# Voeding.net
KiCad netlist of a schematic drawn in Altium Designer
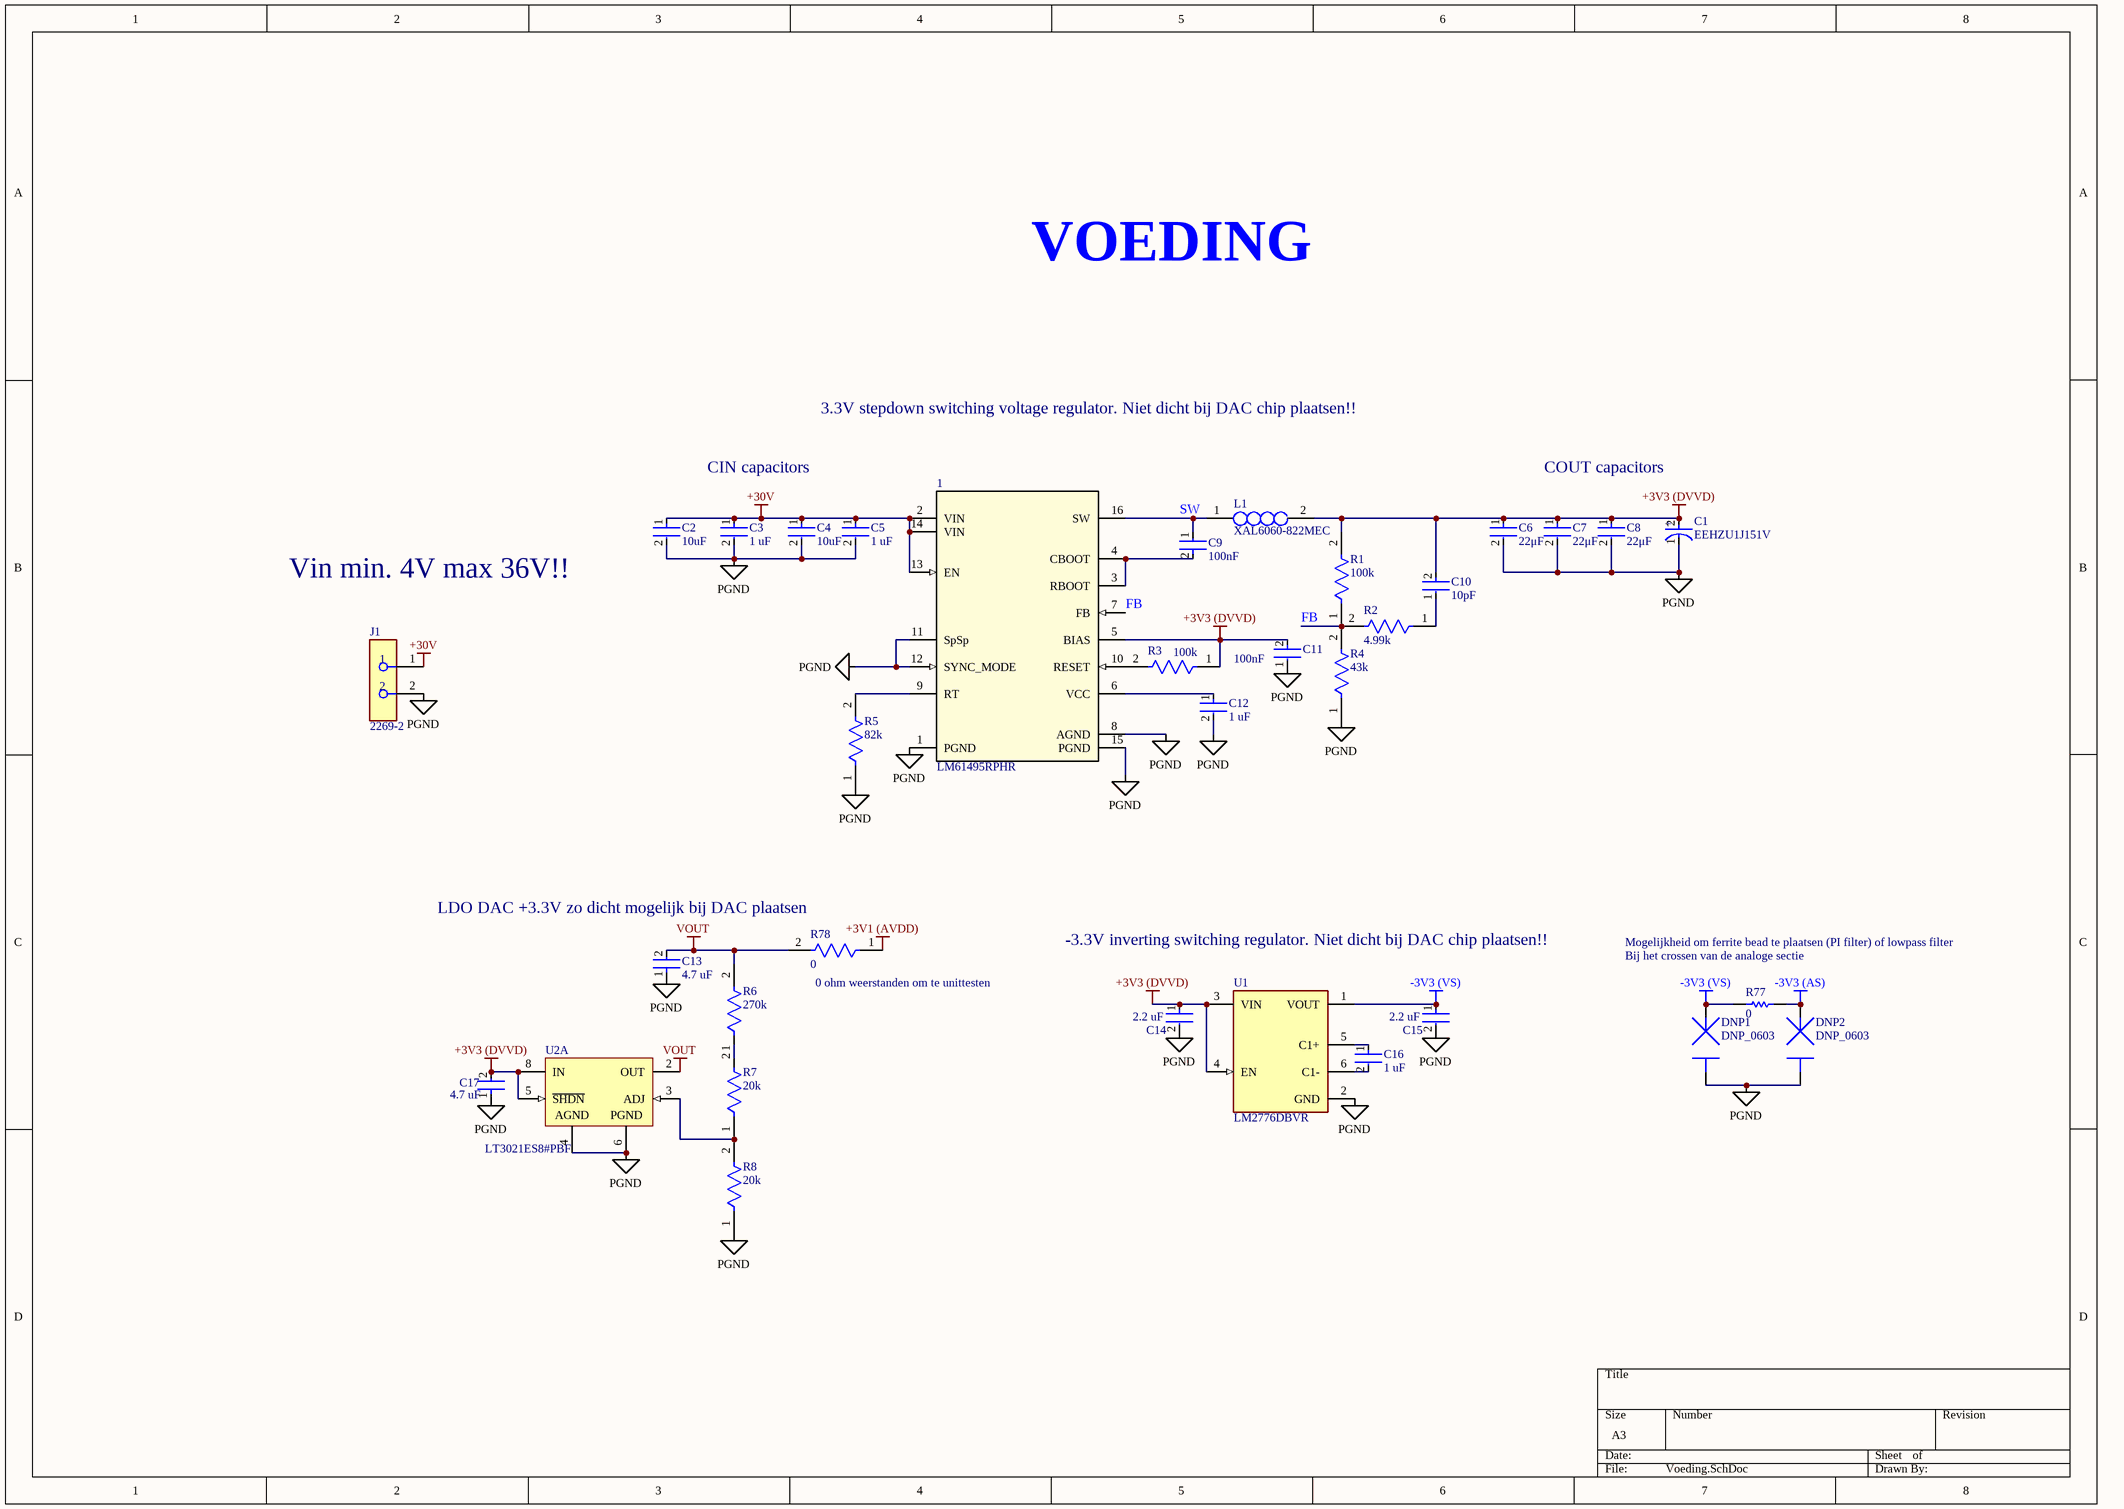
[diagram p0: Voeding.SchDoc]

(export (version "E")
  (design (tool "Eeschema 10.0.6"))
  (components
    (comp (ref "1")
      (value "LM61495RPHR")
      (footprint "RPH0016A")
      (description "No Description Available")
      (libsource (lib "LM61495RPHR") (part "LM61495RPHR"))
    )
    (comp (ref "C1")
      (value "EEHZU1J151V")
      (footprint "FP-EEH-G16-V-MFG")
      (description "Aluminum Hybrid Polymer Capacitors 150uF 20% 63V Life 4000Hours AEC-Q200 RADIAL SMT")
      (libsource (lib "Altium Content Vault") (part "203bc49f2ac43e59fd269a8c329ed05"))
    )
    (comp (ref "C2")
      (value "10uF")
      (footprint "FP-GRM32-MFG")
      (description "CAP CER 10UF 50V X7R 1210")
      (fields (field (name "TOLERANCE") "10%") (field (name "MANUFACTURER PART NUMBER") "GRM32ER71H106KA12L"))
      (libsource (lib "Altium Content Vault") (part "11868f565c42a9108669ba33697ecf6"))
    )
    (comp (ref "C3")
      (value "1 uF")
      (footprint "FP-C0603C-CF-MFG")
      (description "CAP CER 1 UF 50V 5% X7R 0603")
      (fields (field (name "TOLERANCE") "0.05") (field (name "MANUFACTURER PART NUMBER") "C0603C104J5RACTU"))
      (libsource (lib "Altium Content Vault") (part "b4654b650e69147ec39a6b967a45e02"))
    )
    (comp (ref "C4")
      (value "10uF")
      (footprint "FP-GRM32-MFG")
      (description "CAP CER 10UF 50V X7R 1210")
      (fields (field (name "TOLERANCE") "10%") (field (name "MANUFACTURER PART NUMBER") "GRM32ER71H106KA12L"))
      (libsource (lib "Altium Content Vault") (part "11868f565c42a9108669ba33697ecf6"))
    )
    (comp (ref "C5")
      (value "1 uF")
      (footprint "FP-C0603C-CF-MFG")
      (description "CAP CER 1 UF 50V 5% X7R 0603")
      (fields (field (name "TOLERANCE") "0.05") (field (name "MANUFACTURER PART NUMBER") "C0603C104J5RACTU"))
      (libsource (lib "Altium Content Vault") (part "b4654b650e69147ec39a6b967a45e02"))
    )
    (comp (ref "C6")
      (value "22μF")
      (footprint "FP-C2012-125-0_2-MFG")
      (description "Multilayer Ceramic Capacitors 22μF ±20% 10V X5R SMD 0805")
      (fields (field (name "TOLERANCE") "20%"))
      (libsource (lib "Altium Content Vault") (part "b4654b650e69147ec39a6b967a45e02"))
    )
    (comp (ref "C7")
      (value "22μF")
      (footprint "FP-C2012-125-0_2-MFG")
      (description "Multilayer Ceramic Capacitors 22μF ±20% 10V X5R SMD 0805")
      (fields (field (name "TOLERANCE") "20%"))
      (libsource (lib "Altium Content Vault") (part "b4654b650e69147ec39a6b967a45e02"))
    )
    (comp (ref "C8")
      (value "22μF")
      (footprint "FP-C2012-125-0_2-MFG")
      (description "Multilayer Ceramic Capacitors 22μF ±20% 10V X5R SMD 0805")
      (fields (field (name "TOLERANCE") "20%"))
      (libsource (lib "Altium Content Vault") (part "b4654b650e69147ec39a6b967a45e02"))
    )
    (comp (ref "C9")
      (value "100nF")
      (footprint "FP-GRM15-MFG")
      (description "CAP CER 0.1UF 16V X7R 0402")
      (fields (field (name "MANUFACTURER PART NUMBER") "GRM155R71C104KA88D") (field (name "TOLERANCE") "10%"))
      (libsource (lib "Altium Content Vault") (part "236180d848d6139a670b325ea6854c9"))
    )
    (comp (ref "C10")
      (value "10pF")
      (footprint "FP-GRM15-MFG")
      (description "CAP CER 10pF 16V X7R 0402")
      (fields (field (name "MANUFACTURER PART NUMBER") "GRM155R71C104KA88D") (field (name "TOLERANCE") "10%"))
      (libsource (lib "Altium Content Vault") (part "236180d848d6139a670b325ea6854c9"))
    )
    (comp (ref "C11")
      (value "100nF")
      (footprint "FP-GRM15-MFG")
      (description "CAP CER 0.1UF 16V X7R 0402")
      (fields (field (name "MANUFACTURER PART NUMBER") "GRM155R71C104KA88D") (field (name "TOLERANCE") "10%"))
      (libsource (lib "Altium Content Vault") (part "236180d848d6139a670b325ea6854c9"))
    )
    (comp (ref "C12")
      (value "1 uF")
      (footprint "FP-C0603C-CF-MFG")
      (description "CAP CER 1 UF 50V 5% X7R 0603")
      (fields (field (name "TOLERANCE") "0.05") (field (name "MANUFACTURER PART NUMBER") "C0603C104J5RACTU"))
      (libsource (lib "Altium Content Vault") (part "b4654b650e69147ec39a6b967a45e02"))
    )
    (comp (ref "C13")
      (value "4.7 uF")
      (footprint "FP-C0603C-CF-MFG")
      (description "CAP CER 4.7 UF 50V 5% X7R 0603")
      (fields (field (name "TOLERANCE") "0.05") (field (name "MANUFACTURER PART NUMBER") "C0603C104J5RACTU"))
      (libsource (lib "Altium Content Vault") (part "b4654b650e69147ec39a6b967a45e02"))
    )
    (comp (ref "C14")
      (value "2.2 uF")
      (footprint "FP-C0603C-CF-MFG")
      (description "CAP CER 2.2 UF 50V 5% X7R 0603")
      (fields (field (name "TOLERANCE") "0.05") (field (name "MANUFACTURER PART NUMBER") "C0603C104J5RACTU"))
      (libsource (lib "Altium Content Vault") (part "b4654b650e69147ec39a6b967a45e02"))
    )
    (comp (ref "C15")
      (value "2.2 uF")
      (footprint "FP-C0603C-CF-MFG")
      (description "CAP CER 2.2 UF 50V 5% X7R 0603")
      (fields (field (name "TOLERANCE") "0.05") (field (name "MANUFACTURER PART NUMBER") "C0603C104J5RACTU"))
      (libsource (lib "Altium Content Vault") (part "b4654b650e69147ec39a6b967a45e02"))
    )
    (comp (ref "C16")
      (value "1 uF")
      (footprint "FP-C0603C-CF-MFG")
      (description "CAP CER 1 UF 50V 5% X7R 0603")
      (fields (field (name "TOLERANCE") "0.05") (field (name "MANUFACTURER PART NUMBER") "C0603C104J5RACTU"))
      (libsource (lib "Altium Content Vault") (part "b4654b650e69147ec39a6b967a45e02"))
    )
    (comp (ref "C17")
      (value "4.7 uF")
      (footprint "FP-C0603C-CF-MFG")
      (description "CAP CER 4.7 UF 50V 5% X7R 0603")
      (fields (field (name "TOLERANCE") "0.05") (field (name "MANUFACTURER PART NUMBER") "C0603C104J5RACTU"))
      (libsource (lib "Altium Content Vault") (part "b4654b650e69147ec39a6b967a45e02"))
    )
    (comp (ref "DNP1")
      (value "DNP_0603")
      (footprint "DNP_0603_footprint")
      (description "Is just 0603 footprint. So that you can solder 0603 components on it after you ordered youre PCB.")
      (libsource (lib "Schlib2") (part "DNP_0603"))
    )
    (comp (ref "DNP2")
      (value "DNP_0603")
      (footprint "DNP_0603_footprint")
      (description "Is just 0603 footprint. So that you can solder 0603 components on it after you ordered youre PCB.")
      (libsource (lib "Schlib2") (part "DNP_0603"))
    )
    (comp (ref "J1")
      (value "2269-2")
      (footprint "FP-2269-2-MFG")
      (description "CONN DBL BANANA JACK TURRET")
      (libsource (lib "Altium Content Vault") (part "3ddab50f66188bb7952c54a1b76274c"))
    )
    (comp (ref "L1")
      (value "XAL6060-822MEC")
      (footprint "SamacSys:XAL6060822MEC")
      (description "8.2 uH Inductor")
      (fields (field (name "MOUSER PART NUMBER") "994-XAL6060-822MEC"))
      (libsource (lib "*") (part "XAL6060-822MEC"))
    )
    (comp (ref "R1")
      (value "100k")
      (footprint "FP-CRCW0402-C-e3-MFG")
      (description "RES 100K OHM 1% 1/16W 0402")
      (fields (field (name "TOLERANCE") "1%"))
      (libsource (lib "Altium Content Vault") (part "1029c3af85768c4190bb7ad29bc67b5"))
    )
    (comp (ref "R2")
      (value "4.99k")
      (footprint "FP-CRCW0402-e3-MFG")
      (description "RES Thick Film, 4.99kΩ, 1%, 0.063W, 100ppm/°C, 0402")
      (fields (field (name "TOLERANCE") "1%"))
      (libsource (lib "Altium Content Vault") (part "1029c3af85768c4190bb7ad29bc67b5"))
    )
    (comp (ref "R3")
      (value "100k")
      (footprint "FP-CRCW0402-C-e3-MFG")
      (description "RES 100K OHM 1% 1/16W 0402")
      (fields (field (name "TOLERANCE") "1%"))
      (libsource (lib "Altium Content Vault") (part "1029c3af85768c4190bb7ad29bc67b5"))
    )
    (comp (ref "R4")
      (value "43k")
      (footprint "FP-CRCW0402-C-e3-MFG")
      (description "RES 43k OHM 1% 1/16W 0402")
      (fields (field (name "TOLERANCE") "1%"))
      (libsource (lib "Altium Content Vault") (part "1029c3af85768c4190bb7ad29bc67b5"))
    )
    (comp (ref "R5")
      (value "82k")
      (footprint "FP-CRCW0402-C-e3-MFG")
      (description "RES 100K OHM 1% 1/16W 0402")
      (fields (field (name "TOLERANCE") "1%"))
      (libsource (lib "Altium Content Vault") (part "1029c3af85768c4190bb7ad29bc67b5"))
    )
    (comp (ref "R6")
      (value "270k")
      (footprint "FP-ERJ6EN-MFG")
      (description "RES SMD 20K OHM 1% 1/8W 0805")
      (fields (field (name "TOLERANCE") "1%"))
      (libsource (lib "Altium Content Vault") (part "1029c3af85768c4190bb7ad29bc67b5"))
    )
    (comp (ref "R7")
      (value "20k")
      (footprint "FP-ERJ6EN-MFG")
      (description "RES SMD 20K OHM 1% 1/8W 0805")
      (fields (field (name "TOLERANCE") "1%"))
      (libsource (lib "Altium Content Vault") (part "1029c3af85768c4190bb7ad29bc67b5"))
    )
    (comp (ref "R8")
      (value "20k")
      (footprint "FP-ERJ6EN-MFG")
      (description "RES SMD 20K OHM 1% 1/8W 0805")
      (fields (field (name "TOLERANCE") "1%"))
      (libsource (lib "Altium Content Vault") (part "1029c3af85768c4190bb7ad29bc67b5"))
    )
    (comp (ref "R77")
      (value "0")
      (footprint "RESC1608X55X25ML10T15")
      (description "Chip Resistor, 0 Ohm, +/- 5%, 0.1 W, -55 to 155 degC, 0603 (1608 Metric), RoHS, Tape and Reel")
      (fields (field (name "TOLERANCE") "5%") (field (name "MANUFACTURER") "Yageo"))
      (libsource (lib "Altium Content Vault") (part "RES-2"))
    )
    (comp (ref "R78")
      (value "0")
      (footprint "FP-CRCW1206-MFG")
      (description "CRCW12060000ZSTA Zero Ohm Resistor, Jumper, 1206 [3216 Metric], Thick Film, 250 mW, Surface Mount")
      (libsource (lib "Altium Content Vault") (part "1029c3af85768c4190bb7ad29bc67b5"))
    )
    (comp (ref "U1")
      (value "LM2776DBVR")
      (footprint "FP-DBV0006A-MFG")
      (description "IC REG CHARGE PUMP INV SOT23")
      (fields
        (field (name "MANUFACTURER") "Texas Instruments")
        (field (name "OCTOPART") "https://octopart.com/lm2776dbvr-texas+instruments-58839919")
      )
      (libsource (lib "Altium Content Vault") (part "aa1f6f8daf1b38e6829d08268534e6c"))
    )
    (comp (ref "U2")
      (value "LT3021ES8#PBF")
      (footprint "LT-S8-8_L")
      (fields (field (name "MANUFACTURER") "Linear Technology"))
      (libsource (lib "Altium Content Vault") (part "LT-LT3021-S8-8_B"))
    )
  )
  (nets
    (net (code "1") (name "+3V1 (AVDD)") (class "Default")
      (node (ref "R78") (pin "1") (pinfunction "1_1") (pintype "passive"))
    )
    (net (code "2") (name "+3V3 (DVVD)") (class "Default")
      (node (ref "1") (pin "5") (pinfunction "BIAS_5") (pintype "passive"))
      (node (ref "C1") (pin "2") (pinfunction "A_2") (pintype "passive"))
      (node (ref "C10") (pin "2") (pinfunction "2_2") (pintype "passive"))
      (node (ref "C11") (pin "2") (pinfunction "2_2") (pintype "passive"))
      (node (ref "C14") (pin "1") (pinfunction "1_1") (pintype "passive"))
      (node (ref "C17") (pin "2") (pinfunction "2_2") (pintype "passive"))
      (node (ref "C6") (pin "1") (pinfunction "1_1") (pintype "passive"))
      (node (ref "C7") (pin "1") (pinfunction "1_1") (pintype "passive"))
      (node (ref "C8") (pin "1") (pinfunction "1_1") (pintype "passive"))
      (node (ref "L1") (pin "2") (pinfunction "2_2") (pintype "passive"))
      (node (ref "R1") (pin "2") (pinfunction "2_2") (pintype "passive"))
      (node (ref "R3") (pin "1") (pinfunction "1_1") (pintype "passive"))
      (node (ref "U1") (pin "3") (pinfunction "VIN_3") (pintype "power_in"))
      (node (ref "U1") (pin "4") (pinfunction "EN_4") (pintype "input"))
      (node (ref "U2") (pin "5") (pinfunction "~{SHDN}_5") (pintype "input"))
      (node (ref "U2") (pin "8") (pinfunction "IN_8") (pintype "power_in"))
    )
    (net (code "3") (name "+30V") (class "Default")
      (node (ref "1") (pin "13") (pinfunction "EN_13") (pintype "input"))
      (node (ref "1") (pin "14") (pinfunction "VIN_14") (pintype "power_in"))
      (node (ref "1") (pin "2") (pinfunction "VIN_2") (pintype "power_in"))
      (node (ref "C2") (pin "1") (pinfunction "1_1") (pintype "passive"))
      (node (ref "C3") (pin "1") (pinfunction "1_1") (pintype "passive"))
      (node (ref "C4") (pin "1") (pinfunction "1_1") (pintype "passive"))
      (node (ref "C5") (pin "1") (pinfunction "1_1") (pintype "passive"))
      (node (ref "J1") (pin "1") (pinfunction "1_1") (pintype "passive"))
    )
    (net (code "4") (name "-3V3 (AS)") (class "Default")
      (node (ref "DNP2") (pin "2") (pintype "passive"))
      (node (ref "R77") (pin "2") (pinfunction "2_2") (pintype "passive"))
    )
    (net (code "5") (name "-3V3 (VS)") (class "Default")
      (node (ref "C15") (pin "1") (pinfunction "1_1") (pintype "passive"))
      (node (ref "DNP1") (pin "2") (pintype "passive"))
      (node (ref "R77") (pin "1") (pinfunction "1_1") (pintype "passive"))
      (node (ref "U1") (pin "1") (pinfunction "VOUT_1") (pintype "power_in"))
    )
    (net (code "6") (name "/FB") (class "Default")
      (node (ref "1") (pin "7") (pinfunction "FB_7") (pintype "input"))
      (node (ref "R1") (pin "1") (pinfunction "1_1") (pintype "passive"))
      (node (ref "R2") (pin "2") (pinfunction "2_2") (pintype "passive"))
      (node (ref "R4") (pin "2") (pinfunction "2_2") (pintype "passive"))
    )
    (net (code "7") (name "/SW") (class "Default")
      (node (ref "1") (pin "16") (pinfunction "SW_16") (pintype "power_in"))
      (node (ref "C9") (pin "1") (pinfunction "1_1") (pintype "passive"))
      (node (ref "L1") (pin "1") (pinfunction "1_1") (pintype "passive"))
    )
    (net (code "8") (name "Net-(1-CBOOT)") (class "Default")
      (node (ref "1") (pin "3") (pinfunction "RBOOT_3") (pintype "passive"))
      (node (ref "1") (pin "4") (pinfunction "CBOOT_4") (pintype "passive"))
      (node (ref "C9") (pin "2") (pinfunction "2_2") (pintype "passive"))
    )
    (net (code "9") (name "Net-(1-RESET)") (class "Default")
      (node (ref "1") (pin "10") (pinfunction "RESET_10") (pintype "input"))
      (node (ref "R3") (pin "2") (pinfunction "2_2") (pintype "passive"))
    )
    (net (code "10") (name "Net-(1-RT)") (class "Default")
      (node (ref "1") (pin "9") (pinfunction "RT_9") (pintype "passive"))
      (node (ref "R5") (pin "2") (pinfunction "2_2") (pintype "passive"))
    )
    (net (code "11") (name "Net-(1-VCC)") (class "Default")
      (node (ref "1") (pin "6") (pinfunction "VCC_6") (pintype "power_in"))
      (node (ref "C12") (pin "1") (pinfunction "1_1") (pintype "passive"))
    )
    (net (code "12") (name "Net-(C10-Pad1)") (class "Default")
      (node (ref "C10") (pin "1") (pinfunction "1_1") (pintype "passive"))
      (node (ref "R2") (pin "1") (pinfunction "1_1") (pintype "passive"))
    )
    (net (code "13") (name "Net-(R6-Pad1)") (class "Default")
      (node (ref "R6") (pin "1") (pinfunction "1_1") (pintype "passive"))
      (node (ref "R7") (pin "2") (pinfunction "2_2") (pintype "passive"))
    )
    (net (code "14") (name "Net-(U1-C1+)") (class "Default")
      (node (ref "C16") (pin "1") (pinfunction "1_1") (pintype "passive"))
      (node (ref "U1") (pin "5") (pinfunction "C1+_5") (pintype "power_in"))
    )
    (net (code "15") (name "Net-(U1-C1-)") (class "Default")
      (node (ref "C16") (pin "2") (pinfunction "2_2") (pintype "passive"))
      (node (ref "U1") (pin "6") (pinfunction "C1-_6") (pintype "power_in"))
    )
    (net (code "16") (name "Net-(U2A-ADJ)") (class "Default")
      (node (ref "R7") (pin "1") (pinfunction "1_1") (pintype "passive"))
      (node (ref "R8") (pin "2") (pinfunction "2_2") (pintype "passive"))
      (node (ref "U2") (pin "3") (pinfunction "ADJ_3") (pintype "input"))
    )
    (net (code "17") (name "PGND") (class "Default")
      (node (ref "1") (pin "1") (pinfunction "PGND_1") (pintype "power_in"))
      (node (ref "1") (pin "11") (pinfunction "SpSp_11") (pintype "passive"))
      (node (ref "1") (pin "12") (pinfunction "SYNC_MODE_12") (pintype "input"))
      (node (ref "1") (pin "15") (pinfunction "PGND_15") (pintype "power_in"))
      (node (ref "1") (pin "8") (pinfunction "AGND_8") (pintype "power_in"))
      (node (ref "C1") (pin "1") (pinfunction "C_1") (pintype "passive"))
      (node (ref "C11") (pin "1") (pinfunction "1_1") (pintype "passive"))
      (node (ref "C12") (pin "2") (pinfunction "2_2") (pintype "passive"))
      (node (ref "C13") (pin "1") (pinfunction "1_1") (pintype "passive"))
      (node (ref "C14") (pin "2") (pinfunction "2_2") (pintype "passive"))
      (node (ref "C15") (pin "2") (pinfunction "2_2") (pintype "passive"))
      (node (ref "C17") (pin "1") (pinfunction "1_1") (pintype "passive"))
      (node (ref "C2") (pin "2") (pinfunction "2_2") (pintype "passive"))
      (node (ref "C3") (pin "2") (pinfunction "2_2") (pintype "passive"))
      (node (ref "C4") (pin "2") (pinfunction "2_2") (pintype "passive"))
      (node (ref "C5") (pin "2") (pinfunction "2_2") (pintype "passive"))
      (node (ref "C6") (pin "2") (pinfunction "2_2") (pintype "passive"))
      (node (ref "C7") (pin "2") (pinfunction "2_2") (pintype "passive"))
      (node (ref "C8") (pin "2") (pinfunction "2_2") (pintype "passive"))
      (node (ref "DNP1") (pin "1") (pintype "passive"))
      (node (ref "DNP2") (pin "1") (pintype "passive"))
      (node (ref "J1") (pin "2") (pinfunction "2_2") (pintype "passive"))
      (node (ref "R4") (pin "1") (pinfunction "1_1") (pintype "passive"))
      (node (ref "R5") (pin "1") (pinfunction "1_1") (pintype "passive"))
      (node (ref "R8") (pin "1") (pinfunction "1_1") (pintype "passive"))
      (node (ref "U1") (pin "2") (pinfunction "GND_2") (pintype "power_in"))
      (node (ref "U2") (pin "4") (pinfunction "AGND_4") (pintype "power_in"))
      (node (ref "U2") (pin "6") (pinfunction "PGND_6") (pintype "power_in"))
    )
    (net (code "18") (name "VOUT") (class "Default")
      (node (ref "C13") (pin "2") (pinfunction "2_2") (pintype "passive"))
      (node (ref "R6") (pin "2") (pinfunction "2_2") (pintype "passive"))
      (node (ref "R78") (pin "2") (pinfunction "2_2") (pintype "passive"))
      (node (ref "U2") (pin "2") (pinfunction "OUT_2") (pintype "power_in"))
    )
  )
)
